# Tx_328p.net
KiCad netlist of a schematic drawn in EAGLE
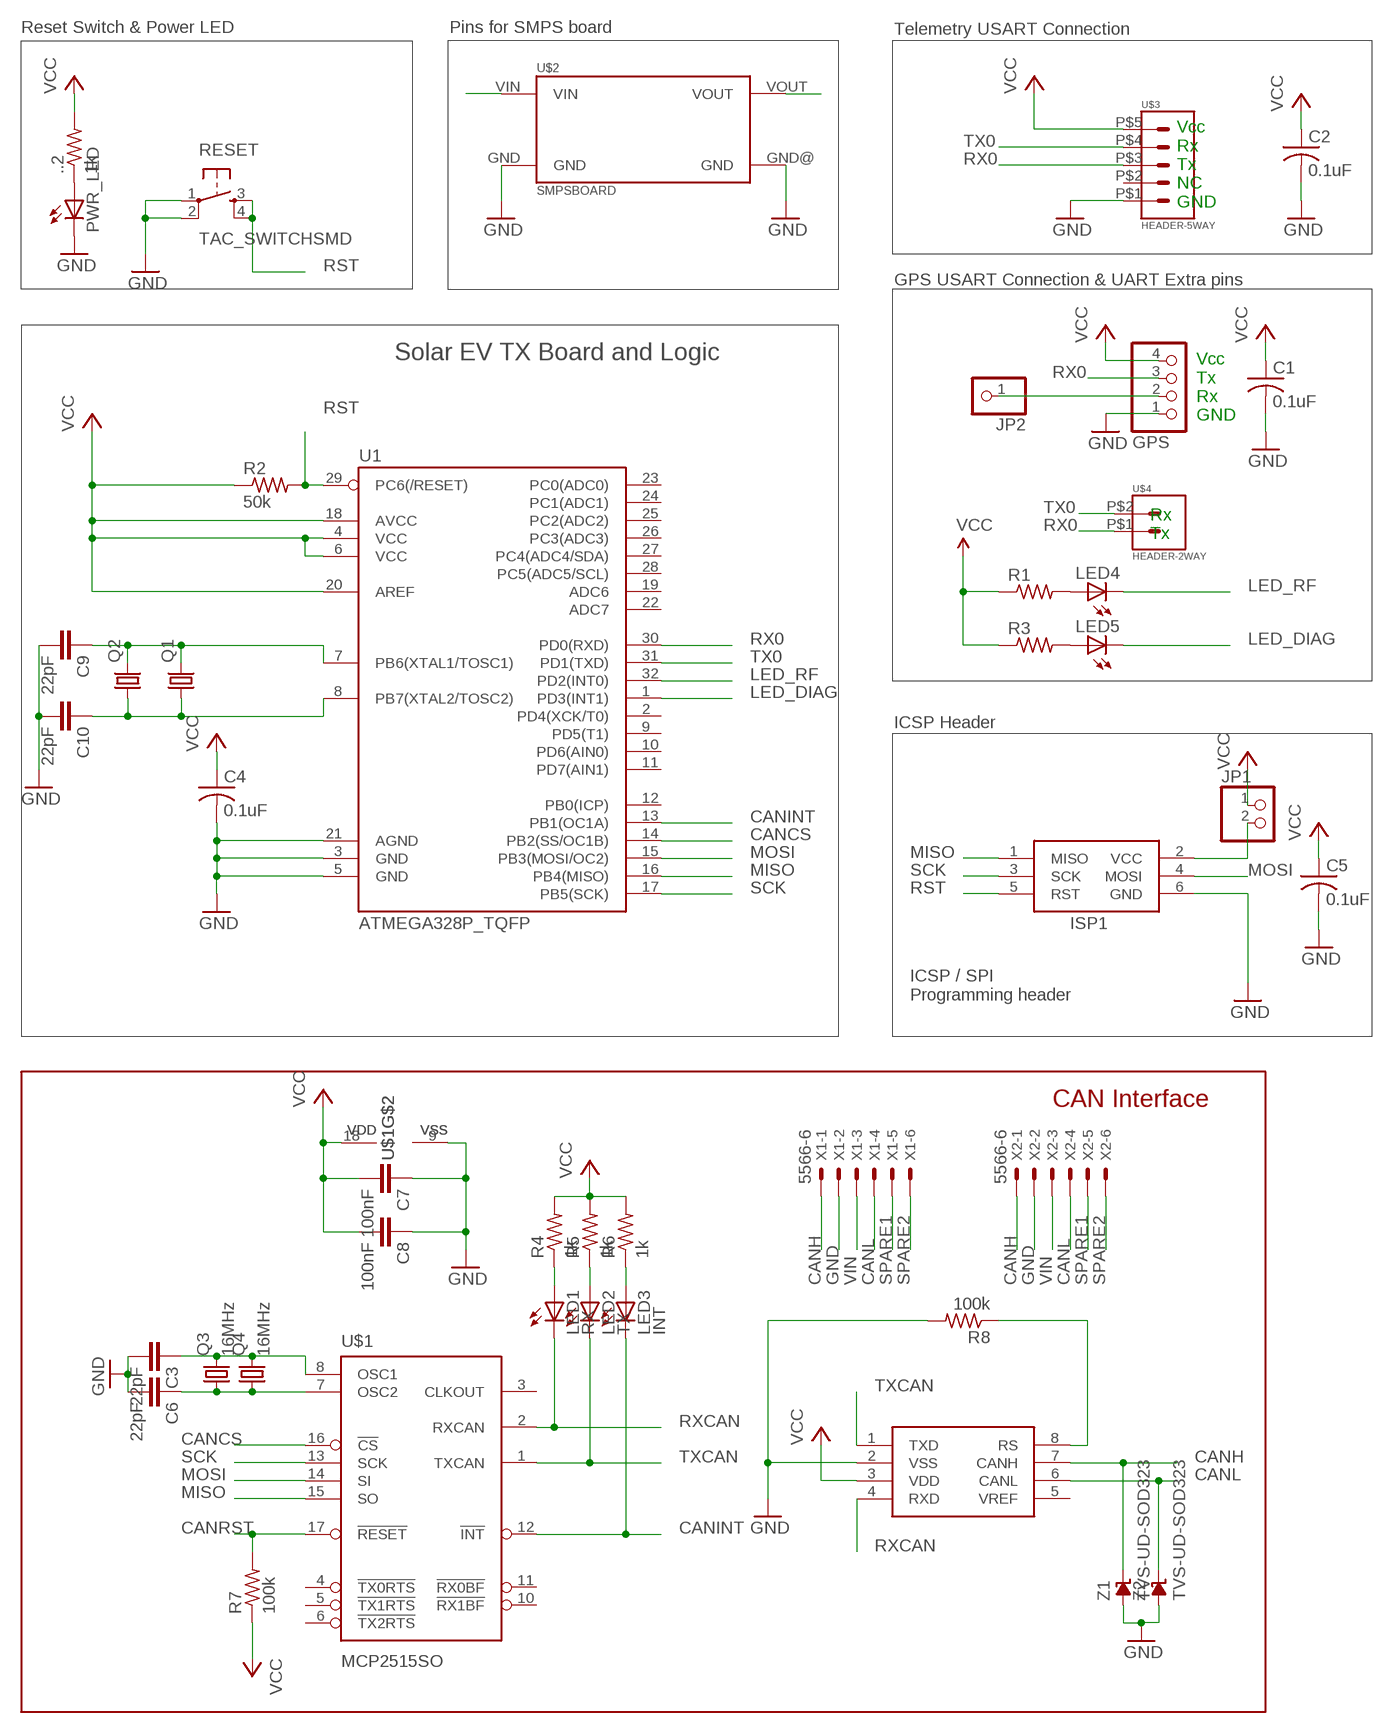
[diagram p0: schematic, sheet 1]

(export (version "E")
  (design (tool "Eeschema 10.0.6"))
  (components
    (comp (ref "..2")
      (value "1k")
      (footprint "eagle-import:M0805")
      (libsource (lib "eagle-import") (part "R-US_M0805"))
    )
    (comp (ref "C1")
      (value "0.1uF")
      (footprint "eagle-import:C0805")
      (libsource (lib "eagle-import") (part "C-USC0805"))
    )
    (comp (ref "C2")
      (value "0.1uF")
      (footprint "eagle-import:C0805")
      (libsource (lib "eagle-import") (part "C-USC0805"))
    )
    (comp (ref "C3")
      (value "22pF")
      (footprint "eagle-import:C0805K")
      (libsource (lib "eagle-import") (part "C-EUC0805K"))
    )
    (comp (ref "C4")
      (value "0.1uF")
      (footprint "eagle-import:C0805")
      (libsource (lib "eagle-import") (part "C-USC0805"))
    )
    (comp (ref "C5")
      (value "0.1uF")
      (footprint "eagle-import:C0805")
      (libsource (lib "eagle-import") (part "C-USC0805"))
    )
    (comp (ref "C6")
      (value "22pF")
      (footprint "eagle-import:C0805K")
      (libsource (lib "eagle-import") (part "C-EUC0805K"))
    )
    (comp (ref "C7")
      (value "100nF")
      (footprint "eagle-import:C0805K")
      (libsource (lib "eagle-import") (part "C-EUC0805K"))
    )
    (comp (ref "C8")
      (value "100nF")
      (footprint "eagle-import:C0805K")
      (libsource (lib "eagle-import") (part "C-EUC0805K"))
    )
    (comp (ref "C9")
      (value "22pF")
      (footprint "eagle-import:C0805K")
      (libsource (lib "eagle-import") (part "C-EUC0805K"))
    )
    (comp (ref "C10")
      (value "22pF")
      (footprint "eagle-import:C0805K")
      (libsource (lib "eagle-import") (part "C-EUC0805K"))
    )
    (comp (ref "GPS")
      (value "PINHD-1X4")
      (footprint "eagle-import:1X04")
      (libsource (lib "eagle-import") (part "PINHD-1X4"))
    )
    (comp (ref "ISP1")
      (value "AVRISP-BOX")
      (footprint "eagle-import:AVRISP-BOX")
      (libsource (lib "eagle-import") (part "AVRISP-BOX"))
    )
    (comp (ref "JP1")
      (value "PINHD-1X2")
      (footprint "eagle-import:1X02")
      (libsource (lib "eagle-import") (part "PINHD-1X2"))
    )
    (comp (ref "JP2")
      (value "PINHD-1X1")
      (footprint "eagle-import:1X01")
      (libsource (lib "eagle-import") (part "PINHD-1X1"))
    )
    (comp (ref "LED1")
      (value "RX")
      (footprint "eagle-import:CHIP-LED0805")
      (libsource (lib "eagle-import") (part "LEDCHIP-LED0805"))
    )
    (comp (ref "LED2")
      (value "TX")
      (footprint "eagle-import:CHIP-LED0805")
      (libsource (lib "eagle-import") (part "LEDCHIP-LED0805"))
    )
    (comp (ref "LED3")
      (value "INT")
      (footprint "eagle-import:CHIP-LED0805")
      (libsource (lib "eagle-import") (part "LEDCHIP-LED0805"))
    )
    (comp (ref "LED4")
      (value "LEDSML0805")
      (footprint "eagle-import:SML0805")
      (libsource (lib "eagle-import") (part "LEDSML0805"))
    )
    (comp (ref "LED5")
      (value "LEDSML0805")
      (footprint "eagle-import:SML0805")
      (libsource (lib "eagle-import") (part "LEDSML0805"))
    )
    (comp (ref "PWR_LED")
      (value "LEDCHIP-LED0805")
      (footprint "eagle-import:CHIP-LED0805")
      (libsource (lib "eagle-import") (part "LEDCHIP-LED0805"))
    )
    (comp (ref "Q1")
      (value "CRYSTALHC49S")
      (footprint "eagle-import:HC49_S")
      (libsource (lib "eagle-import") (part "CRYSTALHC49S"))
    )
    (comp (ref "Q2")
      (value "CRYSTALSM49")
      (footprint "eagle-import:SM49")
      (libsource (lib "eagle-import") (part "CRYSTALSM49"))
    )
    (comp (ref "Q3")
      (value "16MHz")
      (footprint "eagle-import:HC49_S")
      (libsource (lib "eagle-import") (part "CRYSTALHC49S"))
    )
    (comp (ref "Q4")
      (value "16MHz")
      (footprint "eagle-import:HC49UP")
      (libsource (lib "eagle-import") (part "CRYSTALHC49UP"))
    )
    (comp (ref "R1")
      (value "R-US_M0805")
      (footprint "eagle-import:M0805")
      (libsource (lib "eagle-import") (part "resistor_R-US_M0805"))
    )
    (comp (ref "R2")
      (value "50k")
      (footprint "eagle-import:M0805")
      (libsource (lib "eagle-import") (part "resistor_R-US_M0805"))
    )
    (comp (ref "R3")
      (value "R-US_M0805")
      (footprint "eagle-import:M0805")
      (libsource (lib "eagle-import") (part "resistor_R-US_M0805"))
    )
    (comp (ref "R4")
      (value "1k")
      (footprint "eagle-import:R0805")
      (libsource (lib "eagle-import") (part "resistor_R-US_R0805"))
    )
    (comp (ref "R5")
      (value "1k")
      (footprint "eagle-import:R0805")
      (libsource (lib "eagle-import") (part "resistor_R-US_R0805"))
    )
    (comp (ref "R6")
      (value "1k")
      (footprint "eagle-import:R0805")
      (libsource (lib "eagle-import") (part "resistor_R-US_R0805"))
    )
    (comp (ref "R7")
      (value "100k")
      (footprint "eagle-import:R0805")
      (libsource (lib "eagle-import") (part "resistor_R-US_R0805"))
    )
    (comp (ref "R8")
      (value "100k")
      (footprint "eagle-import:R0805")
      (libsource (lib "eagle-import") (part "resistor_R-US_R0805"))
    )
    (comp (ref "RESET")
      (value "TAC_SWITCHSMD")
      (footprint "eagle-import:TACTILE-SWITCH-SMD")
      (libsource (lib "eagle-import") (part "TAC_SWITCHSMD"))
    )
    (comp (ref "U$1")
      (value "MCP2515SO")
      (footprint "eagle-import:SO-18W")
      (libsource (lib "eagle-import") (part "MCP2515SO"))
    )
    (comp (ref "U$2")
      (value "SMPSBOARD")
      (footprint "eagle-import:SMPSBOARD")
      (libsource (lib "eagle-import") (part "SMPSBOARD"))
    )
    (comp (ref "U$3")
      (value "HEADER-5WAY")
      (footprint "eagle-import:1744426-5")
      (libsource (lib "eagle-import") (part "HEADER-5WAY"))
    )
    (comp (ref "U$4")
      (value "HEADER-2WAY")
      (footprint "eagle-import:1744426-2")
      (libsource (lib "eagle-import") (part "HEADER-2WAY"))
    )
    (comp (ref "U1")
      (value "ATMEGA328P_TQFP")
      (footprint "eagle-import:TQFP32-08")
      (libsource (lib "eagle-import") (part "ATMEGA328P_TQFP"))
    )
    (comp (ref "U2")
      (value "MCP2551")
      (footprint "eagle-import:SO08")
      (libsource (lib "eagle-import") (part "MCP2551"))
    )
    (comp (ref "X1")
      (value "5566-6")
      (footprint "eagle-import:5566-6")
      (fields (field (name "MPN") "95566-61002"))
      (libsource (lib "eagle-import") (part "5566-6"))
    )
    (comp (ref "X2")
      (value "5566-6")
      (footprint "eagle-import:5566-6")
      (fields (field (name "MPN") "95566-61002"))
      (libsource (lib "eagle-import") (part "5566-6"))
    )
    (comp (ref "Z1")
      (value "TVS-UD-SOD323")
      (footprint "eagle-import:SOD323")
      (libsource (lib "eagle-import") (part "TVS-UD-SOD323"))
    )
    (comp (ref "Z2")
      (value "TVS-UD-SOD323")
      (footprint "eagle-import:SOD323")
      (libsource (lib "eagle-import") (part "TVS-UD-SOD323"))
    )
  )
  (nets
    (net (code "1") (name "/CANCS") (class "Default")
      (node (ref "U$1") (pin "16") (pinfunction "~{CS}_16") (pintype "input"))
      (node (ref "U1") (pin "14") (pinfunction "PB2(SS/OC1B)_14") (pintype "bidirectional"))
    )
    (net (code "2") (name "/CANH") (class "Default")
      (node (ref "U2") (pin "7") (pinfunction "CANH_7") (pintype "bidirectional"))
      (node (ref "X1") (pin "1") (pinfunction "S_1") (pintype "passive"))
      (node (ref "X2") (pin "1") (pinfunction "S_1") (pintype "passive"))
      (node (ref "Z1") (pin "C") (pinfunction "C_C") (pintype "passive"))
    )
    (net (code "3") (name "/CANINT") (class "Default")
      (node (ref "LED3") (pin "C") (pinfunction "C_C") (pintype "passive"))
      (node (ref "U$1") (pin "12") (pinfunction "~{INT}_12") (pintype "output"))
      (node (ref "U1") (pin "13") (pinfunction "PB1(OC1A)_13") (pintype "bidirectional"))
    )
    (net (code "4") (name "/CANL") (class "Default")
      (node (ref "U2") (pin "6") (pinfunction "CANL_6") (pintype "bidirectional"))
      (node (ref "X1") (pin "4") (pinfunction "S_4") (pintype "passive"))
      (node (ref "X2") (pin "4") (pinfunction "S_4") (pintype "passive"))
      (node (ref "Z2") (pin "C") (pinfunction "C_C") (pintype "passive"))
    )
    (net (code "5") (name "/CANRST") (class "Default")
      (node (ref "R7") (pin "2") (pinfunction "2_2") (pintype "passive"))
      (node (ref "U$1") (pin "17") (pinfunction "~{RESET}_17") (pintype "input"))
    )
    (net (code "6") (name "/LED_DIAG") (class "Default")
      (node (ref "LED5") (pin "C") (pinfunction "C_C") (pintype "passive"))
      (node (ref "U1") (pin "1") (pinfunction "PD3(INT1)_1") (pintype "bidirectional"))
    )
    (net (code "7") (name "/LED_RF") (class "Default")
      (node (ref "LED4") (pin "C") (pinfunction "C_C") (pintype "passive"))
      (node (ref "U1") (pin "32") (pinfunction "PD2(INT0)_32") (pintype "bidirectional"))
    )
    (net (code "8") (name "/MISO") (class "Default")
      (node (ref "ISP1") (pin "1") (pinfunction "MISO_1") (pintype "input"))
      (node (ref "U$1") (pin "15") (pinfunction "SO_15") (pintype "output"))
      (node (ref "U1") (pin "16") (pinfunction "PB4(MISO)_16") (pintype "bidirectional"))
    )
    (net (code "9") (name "/MOSI") (class "Default")
      (node (ref "ISP1") (pin "4") (pinfunction "MOSI_4") (pintype "output"))
      (node (ref "U$1") (pin "14") (pinfunction "SI_14") (pintype "input"))
      (node (ref "U1") (pin "15") (pinfunction "PB3(MOSI/OC2)_15") (pintype "bidirectional"))
    )
    (net (code "10") (name "/RST") (class "Default")
      (node (ref "ISP1") (pin "5") (pinfunction "RST_5") (pintype "output"))
      (node (ref "R2") (pin "2") (pinfunction "2_2") (pintype "passive"))
      (node (ref "RESET") (pin "3") (pinfunction "3_3") (pintype "passive"))
      (node (ref "RESET") (pin "4") (pinfunction "4_4") (pintype "passive"))
      (node (ref "U1") (pin "29") (pinfunction "PC6(/RESET)_29") (pintype "bidirectional"))
    )
    (net (code "11") (name "/RX0") (class "Default")
      (node (ref "GPS") (pin "3") (pinfunction "3_3") (pintype "passive"))
      (node (ref "U$3") (pin "P$3") (pinfunction "P$3_P$3") (pintype "passive"))
      (node (ref "U$4") (pin "P$1") (pinfunction "P$1_P$1") (pintype "passive"))
      (node (ref "U1") (pin "30") (pinfunction "PD0(RXD)_30") (pintype "bidirectional"))
    )
    (net (code "12") (name "/RXCAN") (class "Default")
      (node (ref "LED1") (pin "C") (pinfunction "C_C") (pintype "passive"))
      (node (ref "U$1") (pin "2") (pinfunction "RXCAN_2") (pintype "input"))
      (node (ref "U2") (pin "4") (pinfunction "RXD_4") (pintype "bidirectional"))
    )
    (net (code "13") (name "/SCK") (class "Default")
      (node (ref "ISP1") (pin "3") (pinfunction "SCK_3") (pintype "output"))
      (node (ref "U$1") (pin "13") (pinfunction "SCK_13") (pintype "input"))
      (node (ref "U1") (pin "17") (pinfunction "PB5(SCK)_17") (pintype "bidirectional"))
    )
    (net (code "14") (name "/SPARE1") (class "Default")
      (node (ref "X1") (pin "5") (pinfunction "S_5") (pintype "passive"))
      (node (ref "X2") (pin "5") (pinfunction "S_5") (pintype "passive"))
    )
    (net (code "15") (name "/SPARE2") (class "Default")
      (node (ref "X1") (pin "6") (pinfunction "S_6") (pintype "passive"))
      (node (ref "X2") (pin "6") (pinfunction "S_6") (pintype "passive"))
    )
    (net (code "16") (name "/TX0") (class "Default")
      (node (ref "U$3") (pin "P$4") (pinfunction "P$4_P$4") (pintype "passive"))
      (node (ref "U$4") (pin "P$2") (pinfunction "P$2_P$2") (pintype "passive"))
      (node (ref "U1") (pin "31") (pinfunction "PD1(TXD)_31") (pintype "bidirectional"))
    )
    (net (code "17") (name "/TXCAN") (class "Default")
      (node (ref "LED2") (pin "C") (pinfunction "C_C") (pintype "passive"))
      (node (ref "U$1") (pin "1") (pinfunction "TXCAN_1") (pintype "output"))
      (node (ref "U2") (pin "1") (pinfunction "TXD_1") (pintype "bidirectional"))
    )
    (net (code "18") (name "/VIN") (class "Default")
      (node (ref "U$2") (pin "VIN") (pinfunction "VIN_VIN") (pintype "bidirectional"))
      (node (ref "X1") (pin "3") (pinfunction "S_3") (pintype "passive"))
      (node (ref "X2") (pin "3") (pinfunction "S_3") (pintype "passive"))
    )
    (net (code "19") (name "GND") (class "Default")
      (node (ref "C1") (pin "2") (pinfunction "2_2") (pintype "passive"))
      (node (ref "C10") (pin "2") (pinfunction "2_2") (pintype "passive"))
      (node (ref "C2") (pin "2") (pinfunction "2_2") (pintype "passive"))
      (node (ref "C3") (pin "2") (pinfunction "2_2") (pintype "passive"))
      (node (ref "C4") (pin "2") (pinfunction "2_2") (pintype "passive"))
      (node (ref "C5") (pin "2") (pinfunction "2_2") (pintype "passive"))
      (node (ref "C6") (pin "2") (pinfunction "2_2") (pintype "passive"))
      (node (ref "C7") (pin "1") (pinfunction "1_1") (pintype "passive"))
      (node (ref "C8") (pin "1") (pinfunction "1_1") (pintype "passive"))
      (node (ref "C9") (pin "2") (pinfunction "2_2") (pintype "passive"))
      (node (ref "GPS") (pin "1") (pinfunction "1_1") (pintype "passive"))
      (node (ref "ISP1") (pin "6") (pinfunction "GND_6") (pintype "power_in"))
      (node (ref "PWR_LED") (pin "C") (pinfunction "C_C") (pintype "passive"))
      (node (ref "R8") (pin "2") (pinfunction "2_2") (pintype "passive"))
      (node (ref "RESET") (pin "1") (pinfunction "1_1") (pintype "passive"))
      (node (ref "RESET") (pin "2") (pinfunction "2_2") (pintype "passive"))
      (node (ref "U$1") (pin "9") (pinfunction "VSS_9") (pintype "power_in"))
      (node (ref "U$2") (pin "GND") (pinfunction "GND_GND") (pintype "bidirectional"))
      (node (ref "U$2") (pin "GND@") (pinfunction "GND_GND@") (pintype "bidirectional"))
      (node (ref "U$3") (pin "P$1") (pinfunction "P$1_P$1") (pintype "passive"))
      (node (ref "U1") (pin "21") (pinfunction "AGND_21") (pintype "bidirectional"))
      (node (ref "U1") (pin "3") (pinfunction "GND_3") (pintype "bidirectional"))
      (node (ref "U1") (pin "5") (pinfunction "GND_5") (pintype "bidirectional"))
      (node (ref "U2") (pin "2") (pinfunction "VSS_2") (pintype "bidirectional"))
      (node (ref "X1") (pin "2") (pinfunction "S_2") (pintype "passive"))
      (node (ref "X2") (pin "2") (pinfunction "S_2") (pintype "passive"))
      (node (ref "Z1") (pin "A") (pinfunction "A_A") (pintype "passive"))
      (node (ref "Z2") (pin "A") (pinfunction "A_A") (pintype "passive"))
    )
    (net (code "20") (name "Net-(..2-Pad1)") (class "Default")
      (node (ref "..2") (pin "1") (pinfunction "1_1") (pintype "passive"))
      (node (ref "PWR_LED") (pin "A") (pinfunction "A_A") (pintype "passive"))
    )
    (net (code "21") (name "Net-(GPS-Pad2)") (class "Default")
      (node (ref "GPS") (pin "2") (pinfunction "2_2") (pintype "passive"))
      (node (ref "JP2") (pin "1") (pinfunction "1_1") (pintype "passive"))
    )
    (net (code "22") (name "Net-(ISP1-VCC)") (class "Default")
      (node (ref "ISP1") (pin "2") (pinfunction "VCC_2") (pintype "power_in"))
      (node (ref "JP1") (pin "2") (pinfunction "2_2") (pintype "passive"))
    )
    (net (code "23") (name "Net-(LED1-PadA)") (class "Default")
      (node (ref "LED1") (pin "A") (pinfunction "A_A") (pintype "passive"))
      (node (ref "R4") (pin "1") (pinfunction "1_1") (pintype "passive"))
    )
    (net (code "24") (name "Net-(LED2-PadA)") (class "Default")
      (node (ref "LED2") (pin "A") (pinfunction "A_A") (pintype "passive"))
      (node (ref "R5") (pin "1") (pinfunction "1_1") (pintype "passive"))
    )
    (net (code "25") (name "Net-(LED3-PadA)") (class "Default")
      (node (ref "LED3") (pin "A") (pinfunction "A_A") (pintype "passive"))
      (node (ref "R6") (pin "1") (pinfunction "1_1") (pintype "passive"))
    )
    (net (code "26") (name "Net-(LED4-PadA)") (class "Default")
      (node (ref "LED4") (pin "A") (pinfunction "A_A") (pintype "passive"))
      (node (ref "R1") (pin "2") (pinfunction "2_2") (pintype "passive"))
    )
    (net (code "27") (name "Net-(LED5-PadA)") (class "Default")
      (node (ref "LED5") (pin "A") (pinfunction "A_A") (pintype "passive"))
      (node (ref "R3") (pin "2") (pinfunction "2_2") (pintype "passive"))
    )
    (net (code "28") (name "Net-(U$1A-OSC1)") (class "Default")
      (node (ref "C3") (pin "1") (pinfunction "1_1") (pintype "passive"))
      (node (ref "Q3") (pin "2") (pinfunction "2_2") (pintype "passive"))
      (node (ref "Q4") (pin "2") (pinfunction "2_2") (pintype "passive"))
      (node (ref "U$1") (pin "8") (pinfunction "OSC1_8") (pintype "input"))
    )
    (net (code "29") (name "Net-(U$1A-OSC2)") (class "Default")
      (node (ref "C6") (pin "1") (pinfunction "1_1") (pintype "passive"))
      (node (ref "Q3") (pin "1") (pinfunction "1_1") (pintype "passive"))
      (node (ref "Q4") (pin "1") (pinfunction "1_1") (pintype "passive"))
      (node (ref "U$1") (pin "7") (pinfunction "OSC2_7") (pintype "output"))
    )
    (net (code "30") (name "Net-(U1-PB6(XTAL1{slash}TOSC1))") (class "Default")
      (node (ref "C9") (pin "1") (pinfunction "1_1") (pintype "passive"))
      (node (ref "Q1") (pin "2") (pinfunction "2_2") (pintype "passive"))
      (node (ref "Q2") (pin "2") (pinfunction "2_2") (pintype "passive"))
      (node (ref "U1") (pin "7") (pinfunction "PB6(XTAL1/TOSC1)_7") (pintype "bidirectional"))
    )
    (net (code "31") (name "Net-(U1-PB7(XTAL2{slash}TOSC2))") (class "Default")
      (node (ref "C10") (pin "1") (pinfunction "1_1") (pintype "passive"))
      (node (ref "Q1") (pin "1") (pinfunction "1_1") (pintype "passive"))
      (node (ref "Q2") (pin "1") (pinfunction "1_1") (pintype "passive"))
      (node (ref "U1") (pin "8") (pinfunction "PB7(XTAL2/TOSC2)_8") (pintype "bidirectional"))
    )
    (net (code "32") (name "Net-(U2-RS)") (class "Default")
      (node (ref "R8") (pin "1") (pinfunction "1_1") (pintype "passive"))
      (node (ref "U2") (pin "8") (pinfunction "RS_8") (pintype "bidirectional"))
    )
    (net (code "33") (name "VCC") (class "Default")
      (node (ref "..2") (pin "2") (pinfunction "2_2") (pintype "passive"))
      (node (ref "C1") (pin "1") (pinfunction "1_1") (pintype "passive"))
      (node (ref "C2") (pin "1") (pinfunction "1_1") (pintype "passive"))
      (node (ref "C4") (pin "1") (pinfunction "1_1") (pintype "passive"))
      (node (ref "C5") (pin "1") (pinfunction "1_1") (pintype "passive"))
      (node (ref "C7") (pin "2") (pinfunction "2_2") (pintype "passive"))
      (node (ref "C8") (pin "2") (pinfunction "2_2") (pintype "passive"))
      (node (ref "GPS") (pin "4") (pinfunction "4_4") (pintype "passive"))
      (node (ref "JP1") (pin "1") (pinfunction "1_1") (pintype "passive"))
      (node (ref "R1") (pin "1") (pinfunction "1_1") (pintype "passive"))
      (node (ref "R2") (pin "1") (pinfunction "1_1") (pintype "passive"))
      (node (ref "R3") (pin "1") (pinfunction "1_1") (pintype "passive"))
      (node (ref "R4") (pin "2") (pinfunction "2_2") (pintype "passive"))
      (node (ref "R5") (pin "2") (pinfunction "2_2") (pintype "passive"))
      (node (ref "R6") (pin "2") (pinfunction "2_2") (pintype "passive"))
      (node (ref "R7") (pin "1") (pinfunction "1_1") (pintype "passive"))
      (node (ref "U$1") (pin "18") (pinfunction "VDD_18") (pintype "power_in"))
      (node (ref "U$2") (pin "VOUT") (pinfunction "VOUT_VOUT") (pintype "bidirectional"))
      (node (ref "U$3") (pin "P$5") (pinfunction "P$5_P$5") (pintype "passive"))
      (node (ref "U1") (pin "18") (pinfunction "AVCC_18") (pintype "bidirectional"))
      (node (ref "U1") (pin "20") (pinfunction "AREF_20") (pintype "bidirectional"))
      (node (ref "U1") (pin "4") (pinfunction "VCC_4") (pintype "bidirectional"))
      (node (ref "U1") (pin "6") (pinfunction "VCC_6") (pintype "bidirectional"))
      (node (ref "U2") (pin "3") (pinfunction "VDD_3") (pintype "bidirectional"))
    )
    (net (code "34") (name "unconnected-(U$1A-CLKOUT-Pad3)") (class "Default")
      (node (ref "U$1") (pin "3") (pinfunction "CLKOUT_3") (pintype "output"))
    )
    (net (code "35") (name "unconnected-(U$1A-~{RX0BF}-Pad11)") (class "Default")
      (node (ref "U$1") (pin "11") (pinfunction "~{RX0BF}_11") (pintype "output"))
    )
    (net (code "36") (name "unconnected-(U$1A-~{RX1BF}-Pad10)") (class "Default")
      (node (ref "U$1") (pin "10") (pinfunction "~{RX1BF}_10") (pintype "output"))
    )
    (net (code "37") (name "unconnected-(U$1A-~{TX0RTS}-Pad4)") (class "Default")
      (node (ref "U$1") (pin "4") (pinfunction "~{TX0RTS}_4") (pintype "input"))
    )
    (net (code "38") (name "unconnected-(U$1A-~{TX1RTS}-Pad5)") (class "Default")
      (node (ref "U$1") (pin "5") (pinfunction "~{TX1RTS}_5") (pintype "input"))
    )
    (net (code "39") (name "unconnected-(U$1A-~{TX2RTS}-Pad6)") (class "Default")
      (node (ref "U$1") (pin "6") (pinfunction "~{TX2RTS}_6") (pintype "input"))
    )
    (net (code "40") (name "unconnected-(U$3-PadP$2)") (class "Default")
      (node (ref "U$3") (pin "P$2") (pinfunction "P$2_P$2") (pintype "passive"))
    )
    (net (code "41") (name "unconnected-(U1-ADC6-Pad19)") (class "Default")
      (node (ref "U1") (pin "19") (pinfunction "ADC6_19") (pintype "bidirectional"))
    )
    (net (code "42") (name "unconnected-(U1-ADC7-Pad22)") (class "Default")
      (node (ref "U1") (pin "22") (pinfunction "ADC7_22") (pintype "bidirectional"))
    )
    (net (code "43") (name "unconnected-(U1-PB0(ICP)-Pad12)") (class "Default")
      (node (ref "U1") (pin "12") (pinfunction "PB0(ICP)_12") (pintype "bidirectional"))
    )
    (net (code "44") (name "unconnected-(U1-PC0(ADC0)-Pad23)") (class "Default")
      (node (ref "U1") (pin "23") (pinfunction "PC0(ADC0)_23") (pintype "bidirectional"))
    )
    (net (code "45") (name "unconnected-(U1-PC1(ADC1)-Pad24)") (class "Default")
      (node (ref "U1") (pin "24") (pinfunction "PC1(ADC1)_24") (pintype "bidirectional"))
    )
    (net (code "46") (name "unconnected-(U1-PC2(ADC2)-Pad25)") (class "Default")
      (node (ref "U1") (pin "25") (pinfunction "PC2(ADC2)_25") (pintype "bidirectional"))
    )
    (net (code "47") (name "unconnected-(U1-PC3(ADC3)-Pad26)") (class "Default")
      (node (ref "U1") (pin "26") (pinfunction "PC3(ADC3)_26") (pintype "bidirectional"))
    )
    (net (code "48") (name "unconnected-(U1-PC4(ADC4{slash}SDA)-Pad27)") (class "Default")
      (node (ref "U1") (pin "27") (pinfunction "PC4(ADC4/SDA)_27") (pintype "bidirectional"))
    )
    (net (code "49") (name "unconnected-(U1-PC5(ADC5{slash}SCL)-Pad28)") (class "Default")
      (node (ref "U1") (pin "28") (pinfunction "PC5(ADC5/SCL)_28") (pintype "bidirectional"))
    )
    (net (code "50") (name "unconnected-(U1-PD4(XCK{slash}T0)-Pad2)") (class "Default")
      (node (ref "U1") (pin "2") (pinfunction "PD4(XCK/T0)_2") (pintype "bidirectional"))
    )
    (net (code "51") (name "unconnected-(U1-PD5(T1)-Pad9)") (class "Default")
      (node (ref "U1") (pin "9") (pinfunction "PD5(T1)_9") (pintype "bidirectional"))
    )
    (net (code "52") (name "unconnected-(U1-PD6(AIN0)-Pad10)") (class "Default")
      (node (ref "U1") (pin "10") (pinfunction "PD6(AIN0)_10") (pintype "bidirectional"))
    )
    (net (code "53") (name "unconnected-(U1-PD7(AIN1)-Pad11)") (class "Default")
      (node (ref "U1") (pin "11") (pinfunction "PD7(AIN1)_11") (pintype "bidirectional"))
    )
    (net (code "54") (name "unconnected-(U2-VREF-Pad5)") (class "Default")
      (node (ref "U2") (pin "5") (pinfunction "VREF_5") (pintype "bidirectional"))
    )
  )
)
